# mcu.net
KiCad netlist of a schematic drawn in Altium Designer
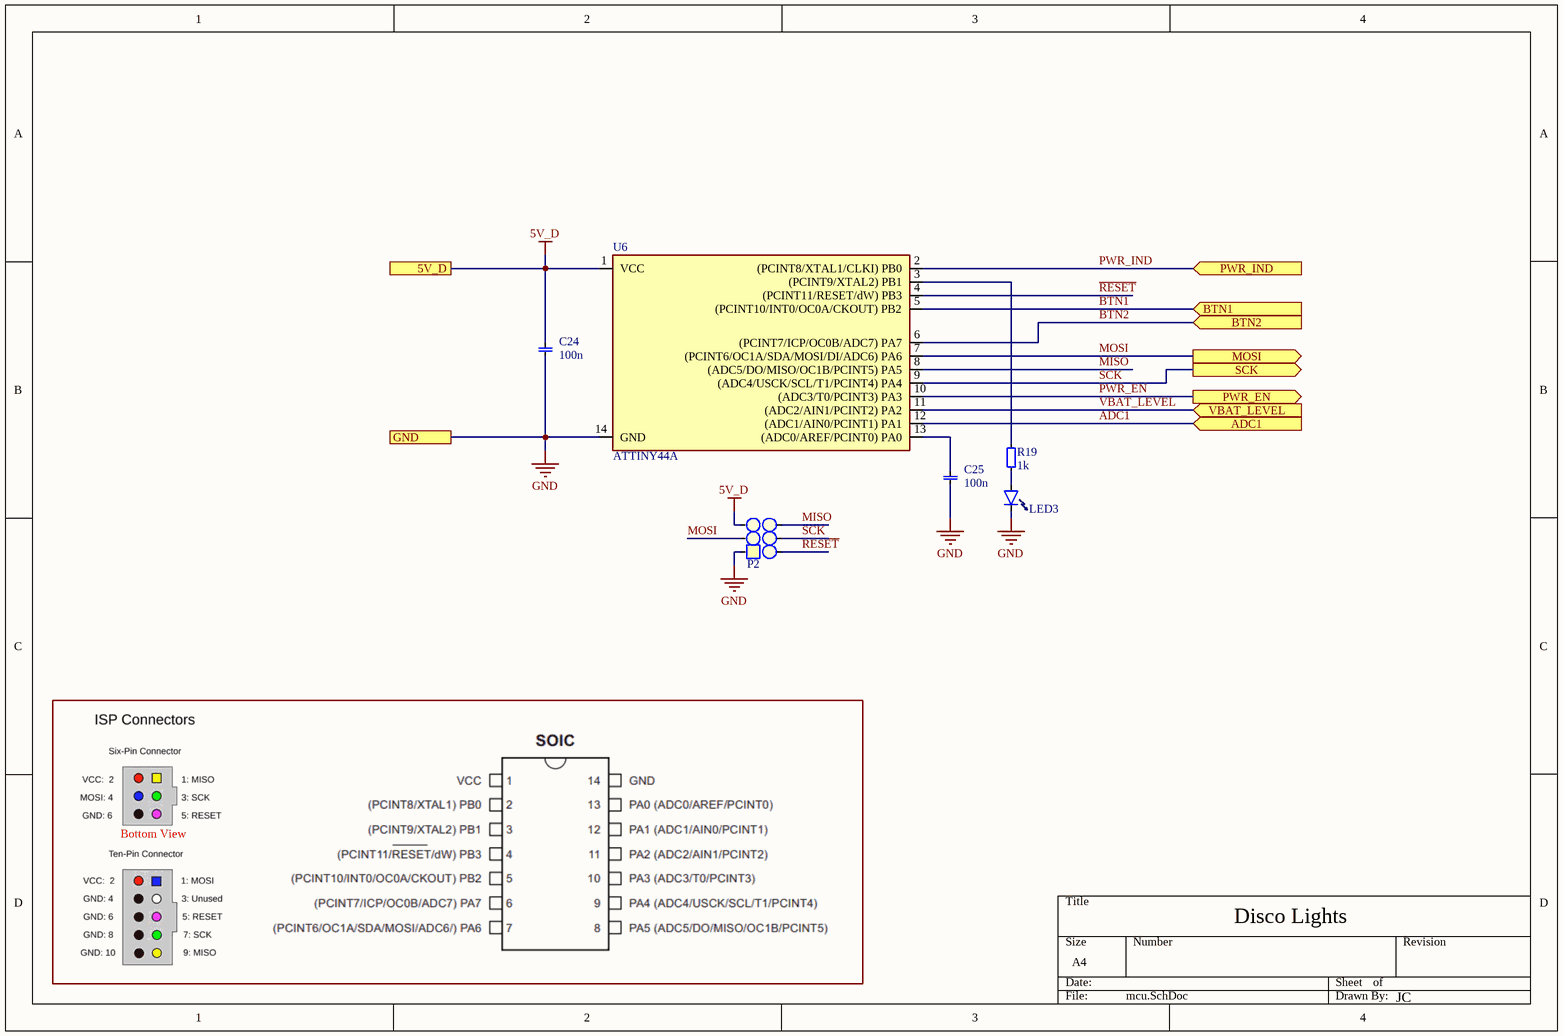
[diagram p0: mcu.SchDoc]

(export (version "E")
  (design (tool "Eeschema 10.0.6"))
  (components
    (comp (ref "C24")
      (value "100n")
      (footprint "0603 cap")
      (fields
        (field (name "JLCPCB PART #") "C14663")
        (field (name "MANUFACTURER PART NUMBER") "CC0603KRX7R9BB102")
        (field (name "Comment") "0603, capacitor")
      )
      (libsource (lib "jclib") (part "0603, capacitor"))
    )
    (comp (ref "C25")
      (value "100n")
      (footprint "0603 cap")
      (fields
        (field (name "JLCPCB PART #") "C14663")
        (field (name "MANUFACTURER PART NUMBER") "CC0603KRX7R9BB102")
        (field (name "Comment") "0603, capacitor")
      )
      (libsource (lib "jclib") (part "0603, capacitor"))
    )
    (comp (ref "LED3")
      (value "0805, LED")
      (footprint "0805_led")
      (fields (field (name "JLCPCB PART #") "C2295") (field (name "MANUFACTURER PART NUMBER") "KP-2012SURCK"))
      (libsource (lib "jclib") (part "0805, LED"))
    )
    (comp (ref "P2")
      (value "2x3 Pin Header")
      (footprint "2x3 PH")
      (libsource (lib "jclib") (part "2x3 Pin Header"))
    )
    (comp (ref "R19")
      (value "1k")
      (footprint "0603")
      (fields
        (field (name "JLCPCB PART #") "C21190")
        (field (name "MANUFACTURER PART NUMBER") "CR0603-FX-1001ELF")
        (field (name "Comment") "0603, resistor")
      )
      (libsource (lib "jclib") (part "0603, resistor"))
    )
    (comp (ref "U6")
      (value "ATTINY44A")
      (footprint "DIP14")
      (description "8-bit microcontrollers based on the AVR® enhanced RISC\r\narchitecture.")
      (fields (field (name "JLCPCB PART #") "C2325"))
      (libsource (lib "jclib") (part "ATTINY44A"))
    )
  )
  (nets
    (net (code "1") (name "/ADC1") (class "Default")
      (node (ref "U6") (pin "12") (pinfunction "(ADC1/AIN0/PCINT1)_PA1_12") (pintype "passive"))
    )
    (net (code "2") (name "/BTN1") (class "Default")
      (node (ref "U6") (pin "5") (pinfunction "(PCINT10/INT0/OC0A/CKOUT)_PB2_5") (pintype "passive"))
    )
    (net (code "3") (name "/BTN2") (class "Default")
      (node (ref "U6") (pin "6") (pinfunction "(PCINT7/ICP/OC0B/ADC7)_PA7_6") (pintype "passive"))
    )
    (net (code "4") (name "/MISO") (class "Default")
      (node (ref "P2") (pin "4") (pinfunction "4_4") (pintype "passive"))
      (node (ref "U6") (pin "8") (pinfunction "(ADC5/DO/MISO/OC1B/PCINT5)_PA5_8") (pintype "passive"))
    )
    (net (code "5") (name "/MOSI") (class "Default")
      (node (ref "P2") (pin "2") (pinfunction "2_2") (pintype "passive"))
      (node (ref "U6") (pin "7") (pinfunction "(PCINT6/OC1A/SDA/MOSI/DI/ADC6)_PA6_7") (pintype "passive"))
    )
    (net (code "6") (name "/PWR_EN") (class "Default")
      (node (ref "U6") (pin "10") (pinfunction "(ADC3/T0/PCINT3)_PA3_10") (pintype "passive"))
    )
    (net (code "7") (name "/PWR_IND") (class "Default")
      (node (ref "U6") (pin "2") (pinfunction "(PCINT8/XTAL1/CLKI)_PB0_2") (pintype "passive"))
    )
    (net (code "8") (name "/SCK") (class "Default")
      (node (ref "P2") (pin "5") (pinfunction "5_5") (pintype "passive"))
      (node (ref "U6") (pin "9") (pinfunction "(ADC4/USCK/SCL/T1/PCINT4)_PA4_9") (pintype "passive"))
    )
    (net (code "9") (name "/VBAT_LEVEL") (class "Default")
      (node (ref "U6") (pin "11") (pinfunction "(ADC2/AIN1/PCINT2)_PA2_11") (pintype "passive"))
    )
    (net (code "10") (name "/~{RESET}") (class "Default")
      (node (ref "P2") (pin "6") (pinfunction "6_6") (pintype "passive"))
      (node (ref "U6") (pin "4") (pinfunction "(PCINT11/RESET/dW)_PB3_4") (pintype "passive"))
    )
    (net (code "11") (name "5V_D") (class "Default")
      (node (ref "C24") (pin "1") (pinfunction "1_1") (pintype "passive"))
      (node (ref "P2") (pin "3") (pinfunction "3_3") (pintype "passive"))
      (node (ref "U6") (pin "1") (pinfunction "VCC_1") (pintype "passive"))
    )
    (net (code "12") (name "GND") (class "Default")
      (node (ref "C24") (pin "0") (pinfunction "0_0") (pintype "passive"))
      (node (ref "C25") (pin "0") (pinfunction "0_0") (pintype "passive"))
      (node (ref "LED3") (pin "0") (pinfunction "Cathode_0") (pintype "passive"))
      (node (ref "P2") (pin "1") (pinfunction "1_1") (pintype "passive"))
      (node (ref "U6") (pin "14") (pinfunction "GND_14") (pintype "passive"))
    )
    (net (code "13") (name "Net-(LED3-Pad1)") (class "Default")
      (node (ref "LED3") (pin "1") (pinfunction "1_1") (pintype "passive"))
      (node (ref "R19") (pin "0") (pinfunction "0_0") (pintype "passive"))
    )
    (net (code "14") (name "Net-(U6-(ADC0{slash}AREF{slash}PCINT0)_PA0)") (class "Default")
      (node (ref "C25") (pin "1") (pinfunction "1_1") (pintype "passive"))
      (node (ref "U6") (pin "13") (pinfunction "(ADC0/AREF/PCINT0)_PA0_13") (pintype "passive"))
    )
    (net (code "15") (name "Net-(U6-(PCINT9{slash}XTAL2)_PB1)") (class "Default")
      (node (ref "R19") (pin "1") (pinfunction "1_1") (pintype "passive"))
      (node (ref "U6") (pin "3") (pinfunction "(PCINT9/XTAL2)_PB1_3") (pintype "passive"))
    )
  )
)
